# interlock.net
KiCad netlist of a schematic drawn in Altium Designer
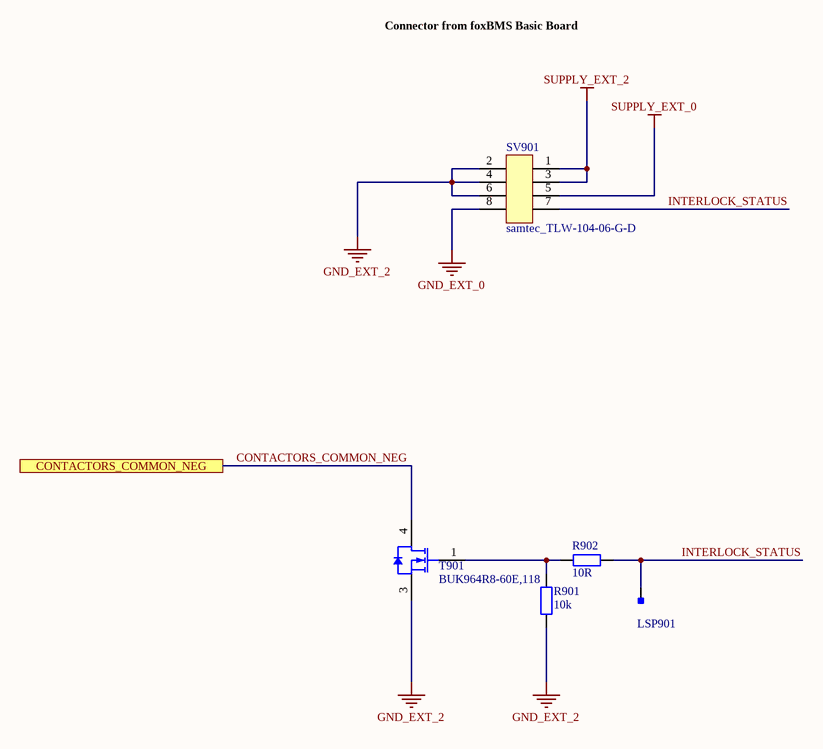
[diagram p0: interlock.SchDoc]

(export (version "E")
  (design (tool "Eeschema 10.0.6"))
  (components
    (comp (ref "LSP901")
      (value "Testpoint_Square")
      (footprint "Testpoint_S1")
      (description "Testpoint, square")
      (libsource (lib "OE750") (part "Testpoint_Square"))
    )
    (comp (ref "R901")
      (value "10k")
      (footprint "RESC1608X05N")
      (description "SMD Resistor 10k 0603")
      (fields (field (name "PART NUMBER") "gen_R_10k_0603") (field (name "TOLERANCE") "1%"))
      (libsource (lib "OE750") (part "R"))
    )
    (comp (ref "R902")
      (value "10R")
      (footprint "RESC1608X05N")
      (description "SMD Resistor 10R 0603")
      (fields (field (name "PART NUMBER") "gen_R_10R_0603") (field (name "TOLERANCE") "1%"))
      (libsource (lib "OE750") (part "R"))
    )
    (comp (ref "SV901")
      (value "samtec_TLW-104-06-G-D")
      (footprint "Pinheader_2.54_2x4")
      (fields (field (name "MANUFACTURER") "Samtec"))
      (libsource (lib "OE750") (part "X2x4"))
    )
    (comp (ref "T901")
      (value "BUK964R8-60E,118")
      (footprint "NXP-SOT404_M")
      (description "N-Channel TrenchMOS Logic Level FET, 60 V, 100 A, 3-Pin SOT404, Tape and Reel")
      (fields (field (name "MANUFACTURER") "NXP Semiconductors"))
      (libsource (lib "Altium Content Vault") (part "NXP-NMOS-GSD-DPAK-3"))
    )
  )
  (nets
    (net (code "1") (name "/CONTACTORS_COMMON_NEG") (class "Default")
      (node (ref "T901") (pin "4") (pinfunction "D_4") (pintype "passive"))
    )
    (net (code "2") (name "/INTERLOCK_STATUS") (class "Default")
      (node (ref "LSP901") (pin "1") (pinfunction "1_1") (pintype "passive"))
      (node (ref "R902") (pin "2") (pinfunction "2_2") (pintype "passive"))
      (node (ref "SV901") (pin "7") (pintype "passive"))
    )
    (net (code "3") (name "GND_EXT_0") (class "Default") (node (ref "SV901") (pin "8") (pintype "passive")))
    (net (code "4") (name "GND_EXT_2") (class "Default")
      (node (ref "R901") (pin "2") (pinfunction "2_2") (pintype "passive"))
      (node (ref "SV901") (pin "2") (pintype "passive"))
      (node (ref "SV901") (pin "4") (pintype "passive"))
      (node (ref "SV901") (pin "6") (pintype "passive"))
      (node (ref "T901") (pin "3") (pinfunction "S_3") (pintype "passive"))
    )
    (net (code "5") (name "Net-(T901-G)") (class "Default")
      (node (ref "R901") (pin "1") (pinfunction "1_1") (pintype "passive"))
      (node (ref "R902") (pin "1") (pinfunction "1_1") (pintype "passive"))
      (node (ref "T901") (pin "1") (pinfunction "G_1") (pintype "passive"))
    )
    (net (code "6") (name "SUPPLY_EXT_0") (class "Default")
      (node (ref "SV901") (pin "5") (pintype "passive"))
    )
    (net (code "7") (name "SUPPLY_EXT_2") (class "Default")
      (node (ref "SV901") (pin "1") (pintype "passive"))
      (node (ref "SV901") (pin "3") (pintype "passive"))
    )
  )
)
